# 7seg_snd2536.net
KiCad netlist of a schematic drawn in EAGLE
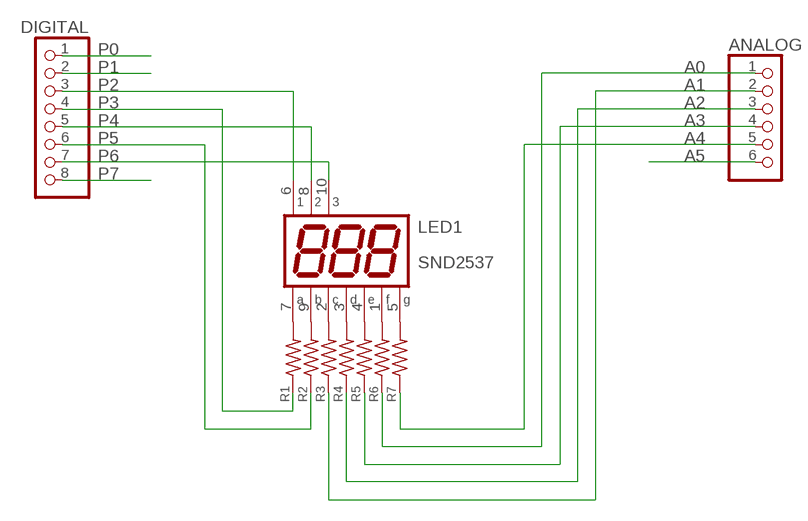
[diagram p0: schematic, sheet 1]

(export (version "E")
  (design (tool "Eeschema 10.0.6"))
  (components
    (comp (ref "ANALOG")
      (value "PINHD-1X6")
      (footprint "eagle-import:1X06")
      (libsource (lib "eagle-import") (part "PINHD-1X6"))
    )
    (comp (ref "DIGITAL")
      (value "PINHD-1X8TH")
      (footprint "eagle-import:1X08-TH")
      (libsource (lib "eagle-import") (part "PINHD-1X8TH"))
    )
    (comp (ref "LED1")
      (value "SND2537")
      (footprint "eagle-import:SND2537-PKG")
      (libsource (lib "eagle-import") (part "SND2537"))
    )
    (comp (ref "R1")
      (value "R-US_0207/10")
      (footprint "eagle-import:0207_10")
      (libsource (lib "eagle-import") (part "R-US_0207/10"))
    )
    (comp (ref "R2")
      (value "R-US_0207/10")
      (footprint "eagle-import:0207_10")
      (libsource (lib "eagle-import") (part "R-US_0207/10"))
    )
    (comp (ref "R3")
      (value "R-US_0207/10")
      (footprint "eagle-import:0207_10")
      (libsource (lib "eagle-import") (part "R-US_0207/10"))
    )
    (comp (ref "R4")
      (value "R-US_0207/10")
      (footprint "eagle-import:0207_10")
      (libsource (lib "eagle-import") (part "R-US_0207/10"))
    )
    (comp (ref "R5")
      (value "R-US_0207/10")
      (footprint "eagle-import:0207_10")
      (libsource (lib "eagle-import") (part "R-US_0207/10"))
    )
    (comp (ref "R6")
      (value "R-US_0207/10")
      (footprint "eagle-import:0207_10")
      (libsource (lib "eagle-import") (part "R-US_0207/10"))
    )
    (comp (ref "R7")
      (value "R-US_0207/10")
      (footprint "eagle-import:0207_10")
      (libsource (lib "eagle-import") (part "R-US_0207/10"))
    )
  )
  (nets
    (net (code "1") (name "/A0") (class "Default")
      (node (ref "ANALOG") (pin "1") (pinfunction "1_1") (pintype "passive"))
      (node (ref "R6") (pin "1") (pinfunction "1_1") (pintype "passive"))
    )
    (net (code "2") (name "/A1") (class "Default")
      (node (ref "ANALOG") (pin "2") (pinfunction "2_2") (pintype "passive"))
      (node (ref "R3") (pin "1") (pinfunction "1_1") (pintype "passive"))
    )
    (net (code "3") (name "/A2") (class "Default")
      (node (ref "ANALOG") (pin "3") (pinfunction "3_3") (pintype "passive"))
      (node (ref "R4") (pin "1") (pinfunction "1_1") (pintype "passive"))
    )
    (net (code "4") (name "/A3") (class "Default")
      (node (ref "ANALOG") (pin "4") (pinfunction "4_4") (pintype "passive"))
      (node (ref "R5") (pin "1") (pinfunction "1_1") (pintype "passive"))
    )
    (net (code "5") (name "/A4") (class "Default")
      (node (ref "ANALOG") (pin "5") (pinfunction "5_5") (pintype "passive"))
      (node (ref "R7") (pin "1") (pinfunction "1_1") (pintype "passive"))
    )
    (net (code "6") (name "/A5") (class "Default")
      (node (ref "ANALOG") (pin "6") (pinfunction "6_6") (pintype "passive"))
    )
    (net (code "7") (name "/P0") (class "Default")
      (node (ref "DIGITAL") (pin "1") (pinfunction "1_1") (pintype "passive"))
    )
    (net (code "8") (name "/P1") (class "Default")
      (node (ref "DIGITAL") (pin "2") (pinfunction "2_2") (pintype "passive"))
    )
    (net (code "9") (name "/P2") (class "Default")
      (node (ref "DIGITAL") (pin "3") (pinfunction "3_3") (pintype "passive"))
      (node (ref "LED1") (pin "6") (pinfunction "1_6") (pintype "passive"))
    )
    (net (code "10") (name "/P3") (class "Default")
      (node (ref "DIGITAL") (pin "4") (pinfunction "4_4") (pintype "passive"))
      (node (ref "R1") (pin "1") (pinfunction "1_1") (pintype "passive"))
    )
    (net (code "11") (name "/P4") (class "Default")
      (node (ref "DIGITAL") (pin "5") (pinfunction "5_5") (pintype "passive"))
      (node (ref "LED1") (pin "8") (pinfunction "2_8") (pintype "passive"))
    )
    (net (code "12") (name "/P5") (class "Default")
      (node (ref "DIGITAL") (pin "6") (pinfunction "6_6") (pintype "passive"))
      (node (ref "R2") (pin "1") (pinfunction "1_1") (pintype "passive"))
    )
    (net (code "13") (name "/P6") (class "Default")
      (node (ref "DIGITAL") (pin "7") (pinfunction "7_7") (pintype "passive"))
      (node (ref "LED1") (pin "10") (pinfunction "3_10") (pintype "passive"))
    )
    (net (code "14") (name "/P7") (class "Default")
      (node (ref "DIGITAL") (pin "8") (pinfunction "8_8") (pintype "passive"))
    )
    (net (code "15") (name "Net-(LED1-A)") (class "Default")
      (node (ref "LED1") (pin "7") (pinfunction "A_7") (pintype "passive"))
      (node (ref "R1") (pin "2") (pinfunction "2_2") (pintype "passive"))
    )
    (net (code "16") (name "Net-(LED1-B)") (class "Default")
      (node (ref "LED1") (pin "9") (pinfunction "B_9") (pintype "passive"))
      (node (ref "R2") (pin "2") (pinfunction "2_2") (pintype "passive"))
    )
    (net (code "17") (name "Net-(LED1-C)") (class "Default")
      (node (ref "LED1") (pin "2") (pinfunction "C_2") (pintype "passive"))
      (node (ref "R3") (pin "2") (pinfunction "2_2") (pintype "passive"))
    )
    (net (code "18") (name "Net-(LED1-D)") (class "Default")
      (node (ref "LED1") (pin "3") (pinfunction "D_3") (pintype "passive"))
      (node (ref "R4") (pin "2") (pinfunction "2_2") (pintype "passive"))
    )
    (net (code "19") (name "Net-(LED1-E)") (class "Default")
      (node (ref "LED1") (pin "4") (pinfunction "E_4") (pintype "passive"))
      (node (ref "R5") (pin "2") (pinfunction "2_2") (pintype "passive"))
    )
    (net (code "20") (name "Net-(LED1-F)") (class "Default")
      (node (ref "LED1") (pin "1") (pinfunction "F_1") (pintype "passive"))
      (node (ref "R6") (pin "2") (pinfunction "2_2") (pintype "passive"))
    )
    (net (code "21") (name "Net-(LED1-G)") (class "Default")
      (node (ref "LED1") (pin "5") (pinfunction "G_5") (pintype "passive"))
      (node (ref "R7") (pin "2") (pinfunction "2_2") (pintype "passive"))
    )
  )
)
